# M4ToVGA.net
KiCad netlist of a schematic drawn in EAGLE
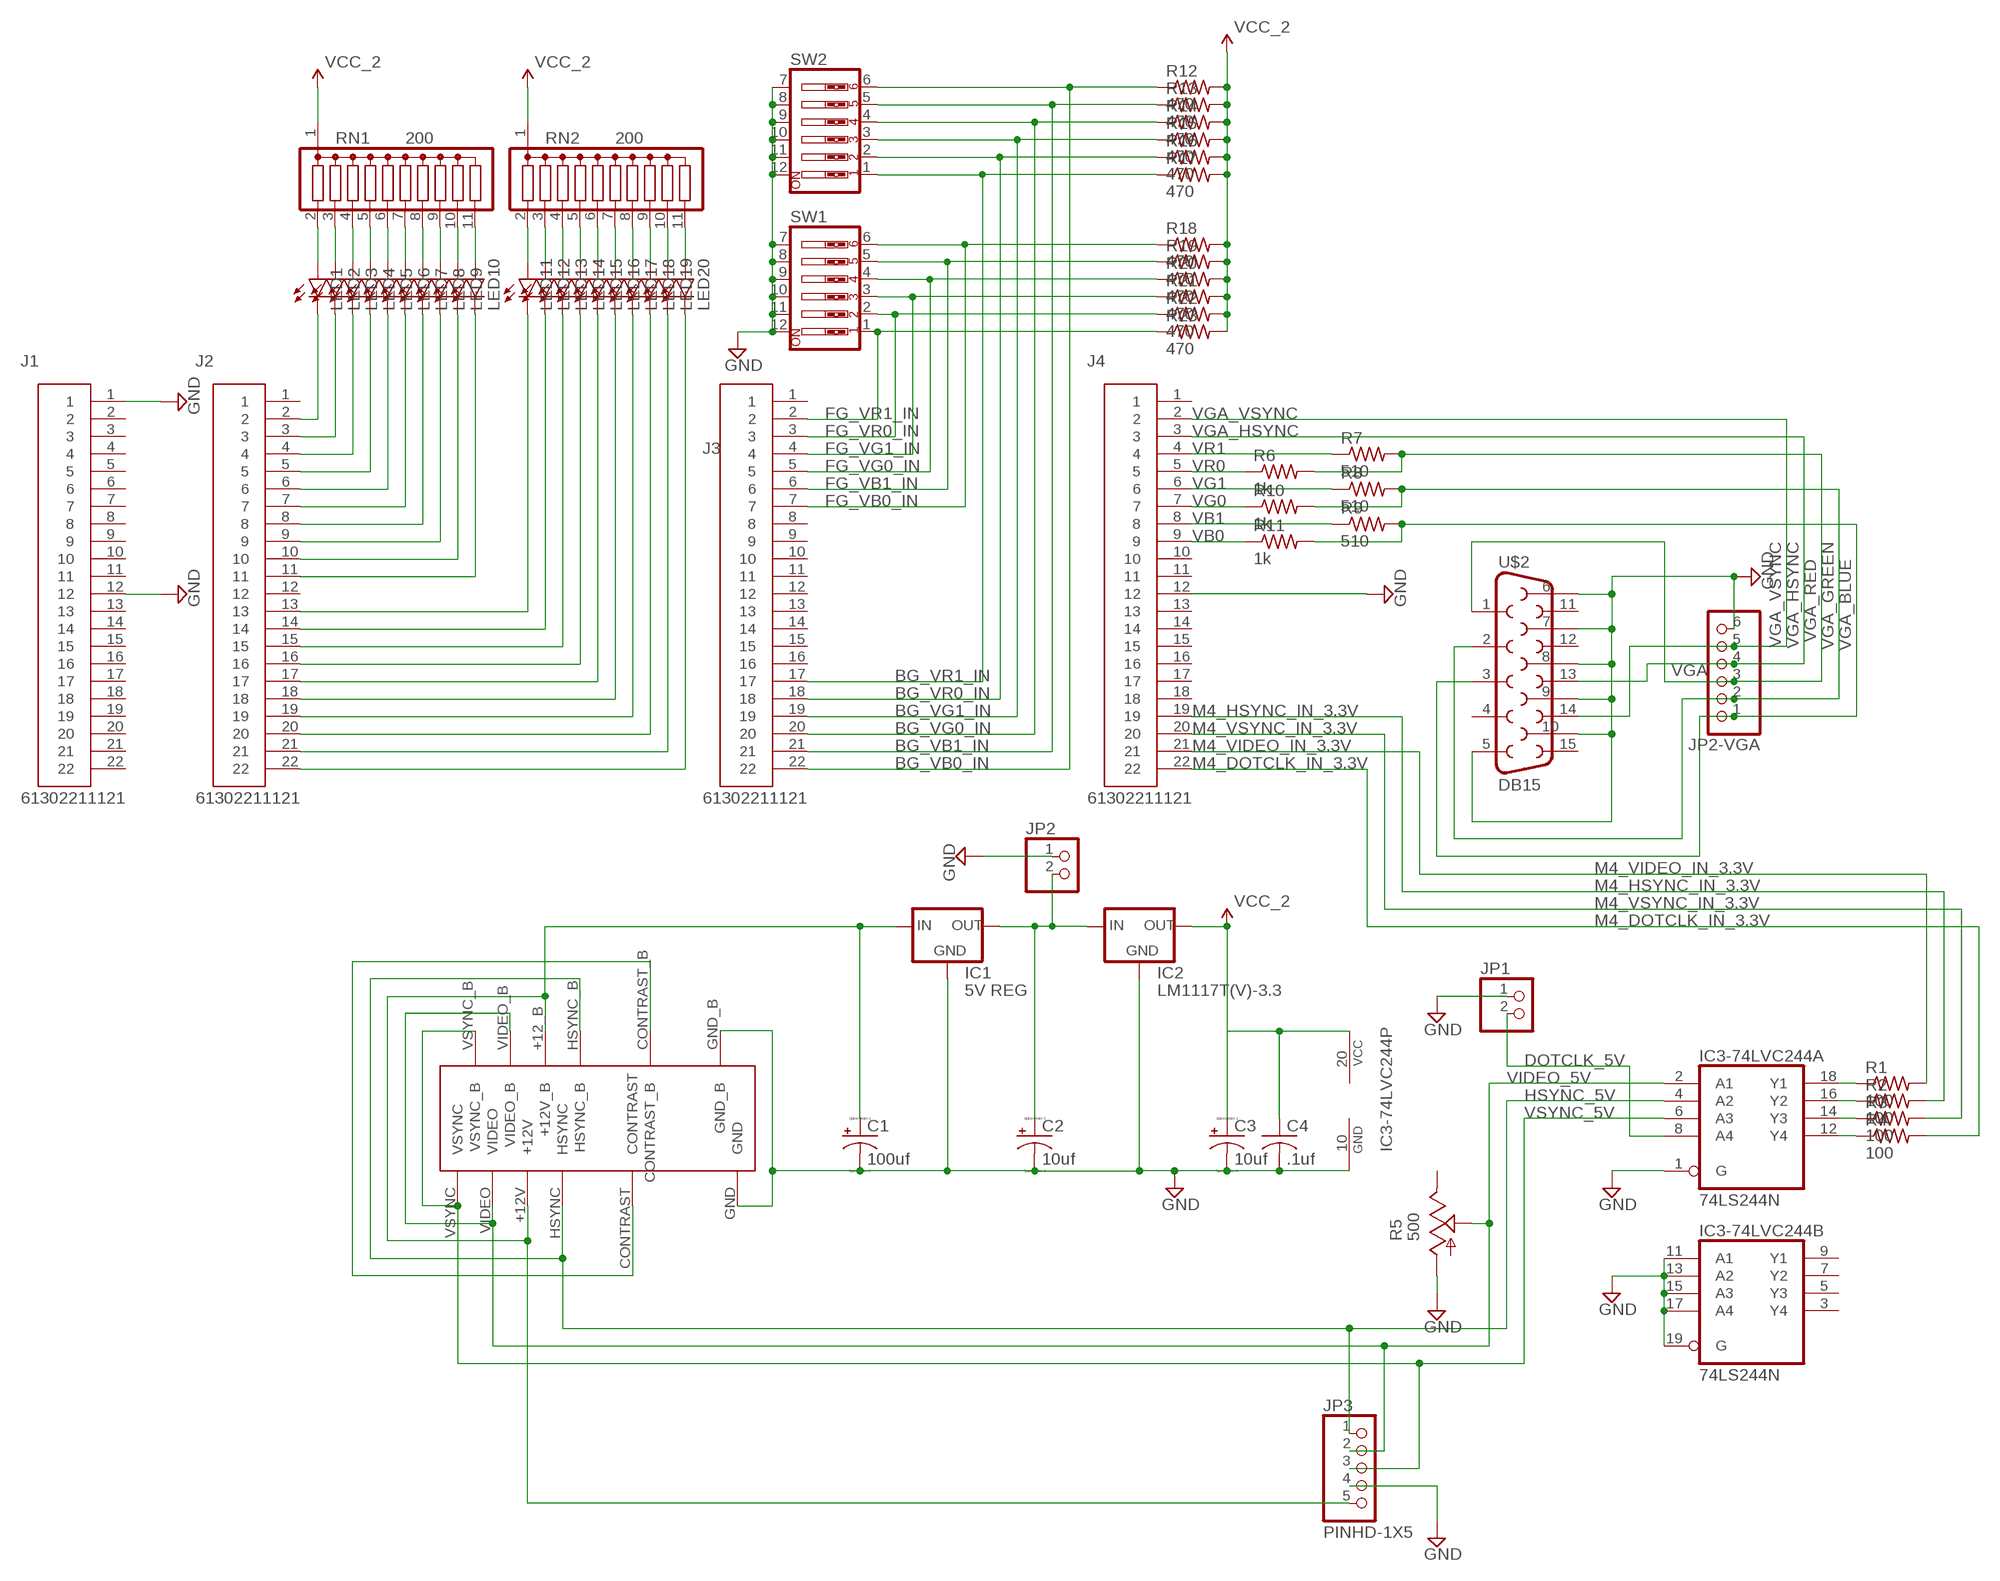
[diagram p0: schematic, sheet 1]

(export (version "E")
  (design (tool "Eeschema 10.0.6"))
  (components
    (comp (ref "C1")
      (value "100uf")
      (footprint "eagle-import:E2,5-5")
      (libsource (lib "eagle-import") (part "CPOL-USE2.5-5"))
    )
    (comp (ref "C2")
      (value "10uf")
      (footprint "eagle-import:E2,5-5")
      (libsource (lib "eagle-import") (part "CPOL-USE2.5-5"))
    )
    (comp (ref "C3")
      (value "10uf")
      (footprint "eagle-import:E2,5-5")
      (libsource (lib "eagle-import") (part "CPOL-USE2.5-5"))
    )
    (comp (ref "C4")
      (value ".1uf")
      (footprint "eagle-import:C025-025X050")
      (libsource (lib "eagle-import") (part "C-US025-025X050"))
    )
    (comp (ref "IC1")
      (value "5V REG")
      (footprint "eagle-import:78XXS")
      (libsource (lib "eagle-import") (part "78XXS"))
    )
    (comp (ref "IC2")
      (value "LM1117T(V)-3.3")
      (footprint "eagle-import:TO220V")
      (fields (field (name "MF") "Texas Instruments") (field (name "MPN") "LM1117T-3.3"))
      (libsource (lib "eagle-import") (part "LM1117?-T(V)3.3"))
    )
    (comp (ref "IC3-74LVC244")
      (value "74LS244N")
      (footprint "eagle-import:DIL20")
      (libsource (lib "eagle-import") (part "74244NLS"))
    )
    (comp (ref "J1")
      (value "61302211121")
      (footprint "eagle-import:61302211121")
      (fields
        (field (name "DIGIKEY_PART_NUMBER") "732-5330-ND")
        (field (name "MANUFACTURER") "Wurth Electronics Inc.")
        (field (name "CREATED_BY") "PCBLayout.com")
      )
      (libsource (lib "eagle-import") (part "61302211121"))
    )
    (comp (ref "J2")
      (value "61302211121")
      (footprint "eagle-import:61302211121")
      (fields
        (field (name "DIGIKEY_PART_NUMBER") "732-5330-ND")
        (field (name "MANUFACTURER") "Wurth Electronics Inc.")
        (field (name "CREATED_BY") "PCBLayout.com")
      )
      (libsource (lib "eagle-import") (part "61302211121"))
    )
    (comp (ref "J3")
      (value "61302211121")
      (footprint "eagle-import:61302211121")
      (fields
        (field (name "DIGIKEY_PART_NUMBER") "732-5330-ND")
        (field (name "MANUFACTURER") "Wurth Electronics Inc.")
        (field (name "CREATED_BY") "PCBLayout.com")
      )
      (libsource (lib "eagle-import") (part "61302211121"))
    )
    (comp (ref "J4")
      (value "61302211121")
      (footprint "eagle-import:61302211121")
      (fields
        (field (name "DIGIKEY_PART_NUMBER") "732-5330-ND")
        (field (name "MANUFACTURER") "Wurth Electronics Inc.")
        (field (name "CREATED_BY") "PCBLayout.com")
      )
      (libsource (lib "eagle-import") (part "61302211121"))
    )
    (comp (ref "JP1")
      (value "PINHD-1X2")
      (footprint "eagle-import:1X02")
      (libsource (lib "eagle-import") (part "PINHD-1X2"))
    )
    (comp (ref "JP2")
      (value "PINHD-1X2")
      (footprint "eagle-import:1X02")
      (libsource (lib "eagle-import") (part "PINHD-1X2"))
    )
    (comp (ref "JP2-VGA")
      (value "VGA")
      (footprint "eagle-import:1X06")
      (libsource (lib "eagle-import") (part "PINHD-1X6"))
    )
    (comp (ref "JP3")
      (value "PINHD-1X5")
      (footprint "eagle-import:1X05")
      (libsource (lib "eagle-import") (part "PINHD-1X5"))
    )
    (comp (ref "LED1")
      (value "LED3MM")
      (footprint "eagle-import:LED3MM")
      (libsource (lib "eagle-import") (part "LED3MM"))
    )
    (comp (ref "LED2")
      (value "LED3MM")
      (footprint "eagle-import:LED3MM")
      (libsource (lib "eagle-import") (part "LED3MM"))
    )
    (comp (ref "LED3")
      (value "LED3MM")
      (footprint "eagle-import:LED3MM")
      (libsource (lib "eagle-import") (part "LED3MM"))
    )
    (comp (ref "LED4")
      (value "LED3MM")
      (footprint "eagle-import:LED3MM")
      (libsource (lib "eagle-import") (part "LED3MM"))
    )
    (comp (ref "LED5")
      (value "LED3MM")
      (footprint "eagle-import:LED3MM")
      (libsource (lib "eagle-import") (part "LED3MM"))
    )
    (comp (ref "LED6")
      (value "LED3MM")
      (footprint "eagle-import:LED3MM")
      (libsource (lib "eagle-import") (part "LED3MM"))
    )
    (comp (ref "LED7")
      (value "LED3MM")
      (footprint "eagle-import:LED3MM")
      (libsource (lib "eagle-import") (part "LED3MM"))
    )
    (comp (ref "LED8")
      (value "LED3MM")
      (footprint "eagle-import:LED3MM")
      (libsource (lib "eagle-import") (part "LED3MM"))
    )
    (comp (ref "LED9")
      (value "LED3MM")
      (footprint "eagle-import:LED3MM")
      (libsource (lib "eagle-import") (part "LED3MM"))
    )
    (comp (ref "LED10")
      (value "LED3MM")
      (footprint "eagle-import:LED3MM")
      (libsource (lib "eagle-import") (part "LED3MM"))
    )
    (comp (ref "LED11")
      (value "LED3MM")
      (footprint "eagle-import:LED3MM")
      (libsource (lib "eagle-import") (part "LED3MM"))
    )
    (comp (ref "LED12")
      (value "LED3MM")
      (footprint "eagle-import:LED3MM")
      (libsource (lib "eagle-import") (part "LED3MM"))
    )
    (comp (ref "LED13")
      (value "LED3MM")
      (footprint "eagle-import:LED3MM")
      (libsource (lib "eagle-import") (part "LED3MM"))
    )
    (comp (ref "LED14")
      (value "LED3MM")
      (footprint "eagle-import:LED3MM")
      (libsource (lib "eagle-import") (part "LED3MM"))
    )
    (comp (ref "LED15")
      (value "LED3MM")
      (footprint "eagle-import:LED3MM")
      (libsource (lib "eagle-import") (part "LED3MM"))
    )
    (comp (ref "LED16")
      (value "LED3MM")
      (footprint "eagle-import:LED3MM")
      (libsource (lib "eagle-import") (part "LED3MM"))
    )
    (comp (ref "LED17")
      (value "LED3MM")
      (footprint "eagle-import:LED3MM")
      (libsource (lib "eagle-import") (part "LED3MM"))
    )
    (comp (ref "LED18")
      (value "LED3MM")
      (footprint "eagle-import:LED3MM")
      (libsource (lib "eagle-import") (part "LED3MM"))
    )
    (comp (ref "LED19")
      (value "LED3MM")
      (footprint "eagle-import:LED3MM")
      (libsource (lib "eagle-import") (part "LED3MM"))
    )
    (comp (ref "LED20")
      (value "LED3MM")
      (footprint "eagle-import:LED3MM")
      (libsource (lib "eagle-import") (part "LED3MM"))
    )
    (comp (ref "R1")
      (value "100")
      (footprint "eagle-import:0204_7")
      (libsource (lib "eagle-import") (part "R-US_0204/7"))
    )
    (comp (ref "R2")
      (value "100")
      (footprint "eagle-import:0204_7")
      (libsource (lib "eagle-import") (part "R-US_0204/7"))
    )
    (comp (ref "R3")
      (value "100")
      (footprint "eagle-import:0204_7")
      (libsource (lib "eagle-import") (part "R-US_0204/7"))
    )
    (comp (ref "R4")
      (value "100")
      (footprint "eagle-import:0204_7")
      (libsource (lib "eagle-import") (part "R-US_0204/7"))
    )
    (comp (ref "R5")
      (value "500")
      (footprint "eagle-import:B25P")
      (libsource (lib "eagle-import") (part "TRIM_US-B25P"))
    )
    (comp (ref "R6")
      (value "1k")
      (footprint "eagle-import:0204_7")
      (libsource (lib "eagle-import") (part "R-US_0204/7"))
    )
    (comp (ref "R7")
      (value "510")
      (footprint "eagle-import:0204_7")
      (libsource (lib "eagle-import") (part "R-US_0204/7"))
    )
    (comp (ref "R8")
      (value "510")
      (footprint "eagle-import:0204_7")
      (libsource (lib "eagle-import") (part "R-US_0204/7"))
    )
    (comp (ref "R9")
      (value "510")
      (footprint "eagle-import:0204_7")
      (libsource (lib "eagle-import") (part "R-US_0204/7"))
    )
    (comp (ref "R10")
      (value "1k")
      (footprint "eagle-import:0204_7")
      (libsource (lib "eagle-import") (part "R-US_0204/7"))
    )
    (comp (ref "R11")
      (value "1k")
      (footprint "eagle-import:0204_7")
      (libsource (lib "eagle-import") (part "R-US_0204/7"))
    )
    (comp (ref "R12")
      (value "470")
      (footprint "eagle-import:0204_7")
      (libsource (lib "eagle-import") (part "R-US_0204/7"))
    )
    (comp (ref "R13")
      (value "470")
      (footprint "eagle-import:0204_7")
      (libsource (lib "eagle-import") (part "R-US_0204/7"))
    )
    (comp (ref "R14")
      (value "470")
      (footprint "eagle-import:0204_7")
      (libsource (lib "eagle-import") (part "R-US_0204/7"))
    )
    (comp (ref "R15")
      (value "470")
      (footprint "eagle-import:0204_7")
      (libsource (lib "eagle-import") (part "R-US_0204/7"))
    )
    (comp (ref "R16")
      (value "470")
      (footprint "eagle-import:0204_7")
      (libsource (lib "eagle-import") (part "R-US_0204/7"))
    )
    (comp (ref "R17")
      (value "470")
      (footprint "eagle-import:0204_7")
      (libsource (lib "eagle-import") (part "R-US_0204/7"))
    )
    (comp (ref "R18")
      (value "470")
      (footprint "eagle-import:0204_7")
      (libsource (lib "eagle-import") (part "R-US_0204/7"))
    )
    (comp (ref "R19")
      (value "470")
      (footprint "eagle-import:0204_7")
      (libsource (lib "eagle-import") (part "R-US_0204/7"))
    )
    (comp (ref "R20")
      (value "470")
      (footprint "eagle-import:0204_7")
      (libsource (lib "eagle-import") (part "R-US_0204/7"))
    )
    (comp (ref "R21")
      (value "470")
      (footprint "eagle-import:0204_7")
      (libsource (lib "eagle-import") (part "R-US_0204/7"))
    )
    (comp (ref "R22")
      (value "470")
      (footprint "eagle-import:0204_7")
      (libsource (lib "eagle-import") (part "R-US_0204/7"))
    )
    (comp (ref "R23")
      (value "470")
      (footprint "eagle-import:0204_7")
      (libsource (lib "eagle-import") (part "R-US_0204/7"))
    )
    (comp (ref "RN1")
      (value "200")
      (footprint "eagle-import:SIL11")
      (libsource (lib "eagle-import") (part "G10R"))
    )
    (comp (ref "RN2")
      (value "200")
      (footprint "eagle-import:SIL11")
      (libsource (lib "eagle-import") (part "G10R"))
    )
    (comp (ref "SW1")
      (value "SW_DIP-6")
      (footprint "eagle-import:EDG-06")
      (libsource (lib "eagle-import") (part "SW_DIP-6"))
    )
    (comp (ref "SW2")
      (value "SW_DIP-6")
      (footprint "eagle-import:EDG-06")
      (libsource (lib "eagle-import") (part "SW_DIP-6"))
    )
    (comp (ref "U$1")
      (value "AMP-583479-1-CARD-EDGE")
      (footprint "eagle-import:AMP583479-1")
      (libsource (lib "eagle-import") (part "AMP-583479-1-CARD-EDGE"))
    )
    (comp (ref "U$2")
      (value "DB15")
      (footprint "eagle-import:DB15")
      (libsource (lib "eagle-import") (part "DB15"))
    )
  )
  (nets
    (net (code "1") (name "/BG_VB0_IN") (class "Default")
      (node (ref "J3") (pin "22") (pinfunction "22_22") (pintype "passive"))
      (node (ref "R12") (pin "1") (pinfunction "1_1") (pintype "passive"))
      (node (ref "SW2") (pin "6") (pinfunction "6_6") (pintype "passive"))
    )
    (net (code "2") (name "/BG_VB1_IN") (class "Default")
      (node (ref "J3") (pin "21") (pinfunction "21_21") (pintype "passive"))
      (node (ref "R13") (pin "1") (pinfunction "1_1") (pintype "passive"))
      (node (ref "SW2") (pin "5") (pinfunction "5_5") (pintype "passive"))
    )
    (net (code "3") (name "/BG_VG0_IN") (class "Default")
      (node (ref "J3") (pin "20") (pinfunction "20_20") (pintype "passive"))
      (node (ref "R14") (pin "1") (pinfunction "1_1") (pintype "passive"))
      (node (ref "SW2") (pin "4") (pinfunction "4_4") (pintype "passive"))
    )
    (net (code "4") (name "/BG_VG1_IN") (class "Default")
      (node (ref "J3") (pin "19") (pinfunction "19_19") (pintype "passive"))
      (node (ref "R15") (pin "1") (pinfunction "1_1") (pintype "passive"))
      (node (ref "SW2") (pin "3") (pinfunction "3_3") (pintype "passive"))
    )
    (net (code "5") (name "/BG_VR0_IN") (class "Default")
      (node (ref "J3") (pin "18") (pinfunction "18_18") (pintype "passive"))
      (node (ref "R16") (pin "1") (pinfunction "1_1") (pintype "passive"))
      (node (ref "SW2") (pin "2") (pinfunction "2_2") (pintype "passive"))
    )
    (net (code "6") (name "/BG_VR1_IN") (class "Default")
      (node (ref "J3") (pin "17") (pinfunction "17_17") (pintype "passive"))
      (node (ref "R17") (pin "1") (pinfunction "1_1") (pintype "passive"))
      (node (ref "SW2") (pin "1") (pinfunction "1_1") (pintype "passive"))
    )
    (net (code "7") (name "/DOTCLK_5V") (class "Default")
      (node (ref "IC3-74LVC244") (pin "8") (pinfunction "A4_8") (pintype "input"))
      (node (ref "JP1") (pin "2") (pinfunction "2_2") (pintype "passive"))
    )
    (net (code "8") (name "/FG_VB0_IN") (class "Default")
      (node (ref "J3") (pin "7") (pinfunction "7_7") (pintype "passive"))
      (node (ref "R18") (pin "1") (pinfunction "1_1") (pintype "passive"))
      (node (ref "SW1") (pin "6") (pinfunction "6_6") (pintype "passive"))
    )
    (net (code "9") (name "/FG_VB1_IN") (class "Default")
      (node (ref "J3") (pin "6") (pinfunction "6_6") (pintype "passive"))
      (node (ref "R19") (pin "1") (pinfunction "1_1") (pintype "passive"))
      (node (ref "SW1") (pin "5") (pinfunction "5_5") (pintype "passive"))
    )
    (net (code "10") (name "/FG_VG0_IN") (class "Default")
      (node (ref "J3") (pin "5") (pinfunction "5_5") (pintype "passive"))
      (node (ref "R20") (pin "1") (pinfunction "1_1") (pintype "passive"))
      (node (ref "SW1") (pin "4") (pinfunction "4_4") (pintype "passive"))
    )
    (net (code "11") (name "/FG_VG1_IN") (class "Default")
      (node (ref "J3") (pin "4") (pinfunction "4_4") (pintype "passive"))
      (node (ref "R21") (pin "1") (pinfunction "1_1") (pintype "passive"))
      (node (ref "SW1") (pin "3") (pinfunction "3_3") (pintype "passive"))
    )
    (net (code "12") (name "/FG_VR0_IN") (class "Default")
      (node (ref "J3") (pin "3") (pinfunction "3_3") (pintype "passive"))
      (node (ref "R22") (pin "1") (pinfunction "1_1") (pintype "passive"))
      (node (ref "SW1") (pin "2") (pinfunction "2_2") (pintype "passive"))
    )
    (net (code "13") (name "/FG_VR1_IN") (class "Default")
      (node (ref "J3") (pin "2") (pinfunction "2_2") (pintype "passive"))
      (node (ref "R23") (pin "1") (pinfunction "1_1") (pintype "passive"))
      (node (ref "SW1") (pin "1") (pinfunction "1_1") (pintype "passive"))
    )
    (net (code "14") (name "/HSYNC_5V") (class "Default")
      (node (ref "IC3-74LVC244") (pin "4") (pinfunction "A2_4") (pintype "input"))
      (node (ref "JP3") (pin "1") (pinfunction "1_1") (pintype "passive"))
      (node (ref "U$1") (pin "HSYNC") (pinfunction "HSYNC_HSYNC") (pintype "bidirectional"))
      (node (ref "U$1") (pin "HSYNC_B") (pinfunction "HSYNC_B_HSYNC_B") (pintype "bidirectional"))
    )
    (net (code "15") (name "/M4_DOTCLK_IN_3.3V") (class "Default")
      (node (ref "J4") (pin "22") (pinfunction "22_22") (pintype "passive"))
      (node (ref "R4") (pin "2") (pinfunction "2_2") (pintype "passive"))
    )
    (net (code "16") (name "/M4_HSYNC_IN_3.3V") (class "Default")
      (node (ref "J4") (pin "19") (pinfunction "19_19") (pintype "passive"))
      (node (ref "R2") (pin "2") (pinfunction "2_2") (pintype "passive"))
    )
    (net (code "17") (name "/M4_VIDEO_IN_3.3V") (class "Default")
      (node (ref "J4") (pin "21") (pinfunction "21_21") (pintype "passive"))
      (node (ref "R1") (pin "2") (pinfunction "2_2") (pintype "passive"))
    )
    (net (code "18") (name "/M4_VSYNC_IN_3.3V") (class "Default")
      (node (ref "J4") (pin "20") (pinfunction "20_20") (pintype "passive"))
      (node (ref "R3") (pin "2") (pinfunction "2_2") (pintype "passive"))
    )
    (net (code "19") (name "/VB0") (class "Default")
      (node (ref "J4") (pin "9") (pinfunction "9_9") (pintype "passive"))
      (node (ref "R11") (pin "1") (pinfunction "1_1") (pintype "passive"))
    )
    (net (code "20") (name "/VB1") (class "Default")
      (node (ref "J4") (pin "8") (pinfunction "8_8") (pintype "passive"))
      (node (ref "R9") (pin "1") (pinfunction "1_1") (pintype "passive"))
    )
    (net (code "21") (name "/VG0") (class "Default")
      (node (ref "J4") (pin "7") (pinfunction "7_7") (pintype "passive"))
      (node (ref "R10") (pin "1") (pinfunction "1_1") (pintype "passive"))
    )
    (net (code "22") (name "/VG1") (class "Default")
      (node (ref "J4") (pin "6") (pinfunction "6_6") (pintype "passive"))
      (node (ref "R8") (pin "1") (pinfunction "1_1") (pintype "passive"))
    )
    (net (code "23") (name "/VGA_BLUE") (class "Default")
      (node (ref "JP2-VGA") (pin "1") (pinfunction "1_1") (pintype "passive"))
      (node (ref "R11") (pin "2") (pinfunction "2_2") (pintype "passive"))
      (node (ref "R9") (pin "2") (pinfunction "2_2") (pintype "passive"))
      (node (ref "U$2") (pin "3") (pinfunction "3_3") (pintype "passive"))
    )
    (net (code "24") (name "/VGA_GREEN") (class "Default")
      (node (ref "JP2-VGA") (pin "2") (pinfunction "2_2") (pintype "passive"))
      (node (ref "R10") (pin "2") (pinfunction "2_2") (pintype "passive"))
      (node (ref "R8") (pin "2") (pinfunction "2_2") (pintype "passive"))
      (node (ref "U$2") (pin "2") (pinfunction "2_2") (pintype "passive"))
    )
    (net (code "25") (name "/VGA_HSYNC") (class "Default")
      (node (ref "J4") (pin "3") (pinfunction "3_3") (pintype "passive"))
      (node (ref "JP2-VGA") (pin "4") (pinfunction "4_4") (pintype "passive"))
      (node (ref "U$2") (pin "13") (pinfunction "13_13") (pintype "passive"))
    )
    (net (code "26") (name "/VGA_RED") (class "Default")
      (node (ref "JP2-VGA") (pin "3") (pinfunction "3_3") (pintype "passive"))
      (node (ref "R6") (pin "2") (pinfunction "2_2") (pintype "passive"))
      (node (ref "R7") (pin "2") (pinfunction "2_2") (pintype "passive"))
      (node (ref "U$2") (pin "1") (pinfunction "1_1") (pintype "passive"))
    )
    (net (code "27") (name "/VGA_VSYNC") (class "Default")
      (node (ref "J4") (pin "2") (pinfunction "2_2") (pintype "passive"))
      (node (ref "JP2-VGA") (pin "5") (pinfunction "5_5") (pintype "passive"))
      (node (ref "U$2") (pin "14") (pinfunction "14_14") (pintype "passive"))
    )
    (net (code "28") (name "/VIDEO_5V") (class "Default")
      (node (ref "IC3-74LVC244") (pin "2") (pinfunction "A1_2") (pintype "input"))
      (node (ref "JP3") (pin "2") (pinfunction "2_2") (pintype "passive"))
      (node (ref "R5") (pin "S") (pinfunction "S_S") (pintype "passive"))
      (node (ref "U$1") (pin "VIDEO") (pinfunction "VIDEO_VIDEO") (pintype "bidirectional"))
      (node (ref "U$1") (pin "VIDEO_B") (pinfunction "VIDEO_B_VIDEO_B") (pintype "bidirectional"))
    )
    (net (code "29") (name "/VR0") (class "Default")
      (node (ref "J4") (pin "5") (pinfunction "5_5") (pintype "passive"))
      (node (ref "R6") (pin "1") (pinfunction "1_1") (pintype "passive"))
    )
    (net (code "30") (name "/VR1") (class "Default")
      (node (ref "J4") (pin "4") (pinfunction "4_4") (pintype "passive"))
      (node (ref "R7") (pin "1") (pinfunction "1_1") (pintype "passive"))
    )
    (net (code "31") (name "/VSYNC_5V") (class "Default")
      (node (ref "IC3-74LVC244") (pin "6") (pinfunction "A3_6") (pintype "input"))
      (node (ref "JP3") (pin "3") (pinfunction "3_3") (pintype "passive"))
      (node (ref "U$1") (pin "VSYNC") (pinfunction "VSYNC_VSYNC") (pintype "bidirectional"))
      (node (ref "U$1") (pin "VSYNC_B") (pinfunction "VSYNC_B_VSYNC_B") (pintype "bidirectional"))
    )
    (net (code "32") (name "GND") (class "Default")
      (node (ref "C1") (pin "-") (pinfunction "-_-") (pintype "passive"))
      (node (ref "C2") (pin "-") (pinfunction "-_-") (pintype "passive"))
      (node (ref "C3") (pin "-") (pinfunction "-_-") (pintype "passive"))
      (node (ref "C4") (pin "2") (pinfunction "2_2") (pintype "passive"))
      (node (ref "IC1") (pin "GND") (pinfunction "GND_GND") (pintype "input"))
      (node (ref "IC2") (pin "1") (pinfunction "GND_1") (pintype "input"))
      (node (ref "IC3-74LVC244") (pin "1") (pinfunction "G_1") (pintype "input"))
      (node (ref "IC3-74LVC244") (pin "10") (pinfunction "GND_10") (pintype "power_in"))
      (node (ref "IC3-74LVC244") (pin "11") (pinfunction "A1_11") (pintype "input"))
      (node (ref "IC3-74LVC244") (pin "13") (pinfunction "A2_13") (pintype "input"))
      (node (ref "IC3-74LVC244") (pin "15") (pinfunction "A3_15") (pintype "input"))
      (node (ref "IC3-74LVC244") (pin "17") (pinfunction "A4_17") (pintype "input"))
      (node (ref "IC3-74LVC244") (pin "19") (pinfunction "G_19") (pintype "input"))
      (node (ref "J1") (pin "1") (pinfunction "1_1") (pintype "passive"))
      (node (ref "J1") (pin "12") (pinfunction "12_12") (pintype "passive"))
      (node (ref "J4") (pin "12") (pinfunction "12_12") (pintype "passive"))
      (node (ref "JP1") (pin "1") (pinfunction "1_1") (pintype "passive"))
      (node (ref "JP2") (pin "1") (pinfunction "1_1") (pintype "passive"))
      (node (ref "JP2-VGA") (pin "6") (pinfunction "6_6") (pintype "passive"))
      (node (ref "JP3") (pin "4") (pinfunction "4_4") (pintype "passive"))
      (node (ref "R5") (pin "A") (pinfunction "A_A") (pintype "passive"))
      (node (ref "SW1") (pin "10") (pinfunction "10_10") (pintype "passive"))
      (node (ref "SW1") (pin "11") (pinfunction "11_11") (pintype "passive"))
      (node (ref "SW1") (pin "12") (pinfunction "12_12") (pintype "passive"))
      (node (ref "SW1") (pin "7") (pinfunction "7_7") (pintype "passive"))
      (node (ref "SW1") (pin "8") (pinfunction "8_8") (pintype "passive"))
      (node (ref "SW1") (pin "9") (pinfunction "9_9") (pintype "passive"))
      (node (ref "SW2") (pin "10") (pinfunction "10_10") (pintype "passive"))
      (node (ref "SW2") (pin "11") (pinfunction "11_11") (pintype "passive"))
      (node (ref "SW2") (pin "12") (pinfunction "12_12") (pintype "passive"))
      (node (ref "SW2") (pin "7") (pinfunction "7_7") (pintype "passive"))
      (node (ref "SW2") (pin "8") (pinfunction "8_8") (pintype "passive"))
      (node (ref "SW2") (pin "9") (pinfunction "9_9") (pintype "passive"))
      (node (ref "U$1") (pin "GND") (pinfunction "GND_GND") (pintype "bidirectional"))
      (node (ref "U$1") (pin "GND_B") (pinfunction "GND_B_GND_B") (pintype "bidirectional"))
      (node (ref "U$2") (pin "10") (pinfunction "10_10") (pintype "passive"))
      (node (ref "U$2") (pin "5") (pinfunction "5_5") (pintype "passive"))
      (node (ref "U$2") (pin "6") (pinfunction "6_6") (pintype "passive"))
      (node (ref "U$2") (pin "7") (pinfunction "7_7") (pintype "passive"))
      (node (ref "U$2") (pin "8") (pinfunction "8_8") (pintype "passive"))
      (node (ref "U$2") (pin "9") (pinfunction "9_9") (pintype "passive"))
    )
    (net (code "33") (name "Net-(IC2-IN)") (class "Default")
      (node (ref "C2") (pin "+") (pinfunction "+_+") (pintype "passive"))
      (node (ref "IC1") (pin "OUT") (pinfunction "OUT_OUT") (pintype "passive"))
      (node (ref "IC2") (pin "3") (pinfunction "IN_3") (pintype "input"))
      (node (ref "JP2") (pin "2") (pinfunction "2_2") (pintype "passive"))
    )
    (net (code "34") (name "Net-(IC3-74LVC244A-Y1)") (class "Default")
      (node (ref "IC3-74LVC244") (pin "18") (pinfunction "Y1_18") (pintype "tri_state"))
      (node (ref "R1") (pin "1") (pinfunction "1_1") (pintype "passive"))
    )
    (net (code "35") (name "Net-(IC3-74LVC244A-Y2)") (class "Default")
      (node (ref "IC3-74LVC244") (pin "16") (pinfunction "Y2_16") (pintype "tri_state"))
      (node (ref "R2") (pin "1") (pinfunction "1_1") (pintype "passive"))
    )
    (net (code "36") (name "Net-(IC3-74LVC244A-Y3)") (class "Default")
      (node (ref "IC3-74LVC244") (pin "14") (pinfunction "Y3_14") (pintype "tri_state"))
      (node (ref "R3") (pin "1") (pinfunction "1_1") (pintype "passive"))
    )
    (net (code "37") (name "Net-(IC3-74LVC244A-Y4)") (class "Default")
      (node (ref "IC3-74LVC244") (pin "12") (pinfunction "Y4_12") (pintype "tri_state"))
      (node (ref "R4") (pin "1") (pinfunction "1_1") (pintype "passive"))
    )
    (net (code "38") (name "Net-(LED1-C)") (class "Default")
      (node (ref "J2") (pin "2") (pinfunction "2_2") (pintype "passive"))
      (node (ref "LED1") (pin "K") (pinfunction "C_K") (pintype "passive"))
    )
    (net (code "39") (name "Net-(LED1-PadA)") (class "Default")
      (node (ref "LED1") (pin "A") (pinfunction "A_A") (pintype "passive"))
      (node (ref "RN1") (pin "2") (pinfunction "2_2") (pintype "passive"))
    )
    (net (code "40") (name "Net-(LED2-C)") (class "Default")
      (node (ref "J2") (pin "3") (pinfunction "3_3") (pintype "passive"))
      (node (ref "LED2") (pin "K") (pinfunction "C_K") (pintype "passive"))
    )
    (net (code "41") (name "Net-(LED2-PadA)") (class "Default")
      (node (ref "LED2") (pin "A") (pinfunction "A_A") (pintype "passive"))
      (node (ref "RN1") (pin "3") (pinfunction "3_3") (pintype "passive"))
    )
    (net (code "42") (name "Net-(LED3-C)") (class "Default")
      (node (ref "J2") (pin "4") (pinfunction "4_4") (pintype "passive"))
      (node (ref "LED3") (pin "K") (pinfunction "C_K") (pintype "passive"))
    )
    (net (code "43") (name "Net-(LED3-PadA)") (class "Default")
      (node (ref "LED3") (pin "A") (pinfunction "A_A") (pintype "passive"))
      (node (ref "RN1") (pin "4") (pinfunction "4_4") (pintype "passive"))
    )
    (net (code "44") (name "Net-(LED4-C)") (class "Default")
      (node (ref "J2") (pin "5") (pinfunction "5_5") (pintype "passive"))
      (node (ref "LED4") (pin "K") (pinfunction "C_K") (pintype "passive"))
    )
    (net (code "45") (name "Net-(LED4-PadA)") (class "Default")
      (node (ref "LED4") (pin "A") (pinfunction "A_A") (pintype "passive"))
      (node (ref "RN1") (pin "5") (pinfunction "5_5") (pintype "passive"))
    )
    (net (code "46") (name "Net-(LED5-C)") (class "Default")
      (node (ref "J2") (pin "6") (pinfunction "6_6") (pintype "passive"))
      (node (ref "LED5") (pin "K") (pinfunction "C_K") (pintype "passive"))
    )
    (net (code "47") (name "Net-(LED5-PadA)") (class "Default")
      (node (ref "LED5") (pin "A") (pinfunction "A_A") (pintype "passive"))
      (node (ref "RN1") (pin "6") (pinfunction "6_6") (pintype "passive"))
    )
    (net (code "48") (name "Net-(LED6-C)") (class "Default")
      (node (ref "J2") (pin "7") (pinfunction "7_7") (pintype "passive"))
      (node (ref "LED6") (pin "K") (pinfunction "C_K") (pintype "passive"))
    )
    (net (code "49") (name "Net-(LED6-PadA)") (class "Default")
      (node (ref "LED6") (pin "A") (pinfunction "A_A") (pintype "passive"))
      (node (ref "RN1") (pin "7") (pinfunction "7_7") (pintype "passive"))
    )
    (net (code "50") (name "Net-(LED7-C)") (class "Default")
      (node (ref "J2") (pin "8") (pinfunction "8_8") (pintype "passive"))
      (node (ref "LED7") (pin "K") (pinfunction "C_K") (pintype "passive"))
    )
    (net (code "51") (name "Net-(LED7-PadA)") (class "Default")
      (node (ref "LED7") (pin "A") (pinfunction "A_A") (pintype "passive"))
      (node (ref "RN1") (pin "8") (pinfunction "8_8") (pintype "passive"))
    )
    (net (code "52") (name "Net-(LED8-C)") (class "Default")
      (node (ref "J2") (pin "9") (pinfunction "9_9") (pintype "passive"))
      (node (ref "LED8") (pin "K") (pinfunction "C_K") (pintype "passive"))
    )
    (net (code "53") (name "Net-(LED8-PadA)") (class "Default")
      (node (ref "LED8") (pin "A") (pinfunction "A_A") (pintype "passive"))
      (node (ref "RN1") (pin "9") (pinfunction "9_9") (pintype "passive"))
    )
    (net (code "54") (name "Net-(LED9-C)") (class "Default")
      (node (ref "J2") (pin "10") (pinfunction "10_10") (pintype "passive"))
      (node (ref "LED9") (pin "K") (pinfunction "C_K") (pintype "passive"))
    )
    (net (code "55") (name "Net-(LED9-PadA)") (class "Default")
      (node (ref "LED9") (pin "A") (pinfunction "A_A") (pintype "passive"))
      (node (ref "RN1") (pin "10") (pinfunction "10_10") (pintype "passive"))
    )
    (net (code "56") (name "Net-(LED10-C)") (class "Default")
      (node (ref "J2") (pin "11") (pinfunction "11_11") (pintype "passive"))
      (node (ref "LED10") (pin "K") (pinfunction "C_K") (pintype "passive"))
    )
    (net (code "57") (name "Net-(LED10-PadA)") (class "Default")
      (node (ref "LED10") (pin "A") (pinfunction "A_A") (pintype "passive"))
      (node (ref "RN1") (pin "11") (pinfunction "11_11") (pintype "passive"))
    )
    (net (code "58") (name "Net-(LED11-C)") (class "Default")
      (node (ref "J2") (pin "13") (pinfunction "13_13") (pintype "passive"))
      (node (ref "LED11") (pin "K") (pinfunction "C_K") (pintype "passive"))
    )
    (net (code "59") (name "Net-(LED11-PadA)") (class "Default")
      (node (ref "LED11") (pin "A") (pinfunction "A_A") (pintype "passive"))
      (node (ref "RN2") (pin "2") (pinfunction "2_2") (pintype "passive"))
    )
    (net (code "60") (name "Net-(LED12-C)") (class "Default")
      (node (ref "J2") (pin "14") (pinfunction "14_14") (pintype "passive"))
      (node (ref "LED12") (pin "K") (pinfunction "C_K") (pintype "passive"))
    )
    (net (code "61") (name "Net-(LED12-PadA)") (class "Default")
      (node (ref "LED12") (pin "A") (pinfunction "A_A") (pintype "passive"))
      (node (ref "RN2") (pin "3") (pinfunction "3_3") (pintype "passive"))
    )
    (net (code "62") (name "Net-(LED13-C)") (class "Default")
      (node (ref "J2") (pin "15") (pinfunction "15_15") (pintype "passive"))
      (node (ref "LED13") (pin "K") (pinfunction "C_K") (pintype "passive"))
    )
    (net (code "63") (name "Net-(LED13-PadA)") (class "Default")
      (node (ref "LED13") (pin "A") (pinfunction "A_A") (pintype "passive"))
      (node (ref "RN2") (pin "4") (pinfunction "4_4") (pintype "passive"))
    )
    (net (code "64") (name "Net-(LED14-C)") (class "Default")
      (node (ref "J2") (pin "16") (pinfunction "16_16") (pintype "passive"))
      (node (ref "LED14") (pin "K") (pinfunction "C_K") (pintype "passive"))
    )
    (net (code "65") (name "Net-(LED14-PadA)") (class "Default")
      (node (ref "LED14") (pin "A") (pinfunction "A_A") (pintype "passive"))
      (node (ref "RN2") (pin "5") (pinfunction "5_5") (pintype "passive"))
    )
    (net (code "66") (name "Net-(LED15-C)") (class "Default")
      (node (ref "J2") (pin "17") (pinfunction "17_17") (pintype "passive"))
      (node (ref "LED15") (pin "K") (pinfunction "C_K") (pintype "passive"))
    )
    (net (code "67") (name "Net-(LED15-PadA)") (class "Default")
      (node (ref "LED15") (pin "A") (pinfunction "A_A") (pintype "passive"))
      (node (ref "RN2") (pin "6") (pinfunction "6_6") (pintype "passive"))
    )
    (net (code "68") (name "Net-(LED16-C)") (class "Default")
      (node (ref "J2") (pin "18") (pinfunction "18_18") (pintype "passive"))
      (node (ref "LED16") (pin "K") (pinfunction "C_K") (pintype "passive"))
    )
    (net (code "69") (name "Net-(LED16-PadA)") (class "Default")
      (node (ref "LED16") (pin "A") (pinfunction "A_A") (pintype "passive"))
      (node (ref "RN2") (pin "7") (pinfunction "7_7") (pintype "passive"))
    )
    (net (code "70") (name "Net-(LED17-C)") (class "Default")
      (node (ref "J2") (pin "19") (pinfunction "19_19") (pintype "passive"))
      (node (ref "LED17") (pin "K") (pinfunction "C_K") (pintype "passive"))
    )
    (net (code "71") (name "Net-(LED17-PadA)") (class "Default")
      (node (ref "LED17") (pin "A") (pinfunction "A_A") (pintype "passive"))
      (node (ref "RN2") (pin "8") (pinfunction "8_8") (pintype "passive"))
    )
    (net (code "72") (name "Net-(LED18-C)") (class "Default")
      (node (ref "J2") (pin "20") (pinfunction "20_20") (pintype "passive"))
      (node (ref "LED18") (pin "K") (pinfunction "C_K") (pintype "passive"))
    )
    (net (code "73") (name "Net-(LED18-PadA)") (class "Default")
      (node (ref "LED18") (pin "A") (pinfunction "A_A") (pintype "passive"))
      (node (ref "RN2") (pin "9") (pinfunction "9_9") (pintype "passive"))
    )
    (net (code "74") (name "Net-(LED19-C)") (class "Default")
      (node (ref "J2") (pin "21") (pinfunction "21_21") (pintype "passive"))
      (node (ref "LED19") (pin "K") (pinfunction "C_K") (pintype "passive"))
    )
    (net (code "75") (name "Net-(LED19-PadA)") (class "Default")
      (node (ref "LED19") (pin "A") (pinfunction "A_A") (pintype "passive"))
      (node (ref "RN2") (pin "10") (pinfunction "10_10") (pintype "passive"))
    )
    (net (code "76") (name "Net-(LED20-C)") (class "Default")
      (node (ref "J2") (pin "22") (pinfunction "22_22") (pintype "passive"))
      (node (ref "LED20") (pin "K") (pinfunction "C_K") (pintype "passive"))
    )
    (net (code "77") (name "Net-(LED20-PadA)") (class "Default")
      (node (ref "LED20") (pin "A") (pinfunction "A_A") (pintype "passive"))
      (node (ref "RN2") (pin "11") (pinfunction "11_11") (pintype "passive"))
    )
    (net (code "78") (name "Net-(U$1-+12V_B)") (class "Default")
      (node (ref "C1") (pin "+") (pinfunction "+_+") (pintype "passive"))
      (node (ref "IC1") (pin "IN") (pinfunction "IN_IN") (pintype "input"))
      (node (ref "JP3") (pin "5") (pinfunction "5_5") (pintype "passive"))
      (node (ref "U$1") (pin "+12V") (pinfunction "+12V_+12V") (pintype "bidirectional"))
      (node (ref "U$1") (pin "+12_B") (pinfunction "+12V_B_+12_B") (pintype "bidirectional"))
    )
    (net (code "79") (name "Net-(U$1-PadCONTRAST)") (class "Default")
      (node (ref "U$1") (pin "CONTRAST") (pinfunction "CONTRAST_CONTRAST") (pintype "bidirectional"))
      (node (ref "U$1") (pin "CONTRAST_B") (pinfunction "CONTRAST_B_CONTRAST_B") (pintype "bidirectional"))
    )
    (net (code "80") (name "VCC_2") (class "Default")
      (node (ref "C3") (pin "+") (pinfunction "+_+") (pintype "passive"))
      (node (ref "C4") (pin "1") (pinfunction "1_1") (pintype "passive"))
      (node (ref "IC2") (pin "2") (pinfunction "OUT_2") (pintype "passive"))
      (node (ref "IC3-74LVC244") (pin "20") (pinfunction "VCC_20") (pintype "power_in"))
      (node (ref "R12") (pin "2") (pinfunction "2_2") (pintype "passive"))
      (node (ref "R13") (pin "2") (pinfunction "2_2") (pintype "passive"))
      (node (ref "R14") (pin "2") (pinfunction "2_2") (pintype "passive"))
      (node (ref "R15") (pin "2") (pinfunction "2_2") (pintype "passive"))
      (node (ref "R16") (pin "2") (pinfunction "2_2") (pintype "passive"))
      (node (ref "R17") (pin "2") (pinfunction "2_2") (pintype "passive"))
      (node (ref "R18") (pin "2") (pinfunction "2_2") (pintype "passive"))
      (node (ref "R19") (pin "2") (pinfunction "2_2") (pintype "passive"))
      (node (ref "R20") (pin "2") (pinfunction "2_2") (pintype "passive"))
      (node (ref "R21") (pin "2") (pinfunction "2_2") (pintype "passive"))
      (node (ref "R22") (pin "2") (pinfunction "2_2") (pintype "passive"))
      (node (ref "R23") (pin "2") (pinfunction "2_2") (pintype "passive"))
      (node (ref "RN1") (pin "1") (pinfunction "1_1") (pintype "passive"))
      (node (ref "RN2") (pin "1") (pinfunction "1_1") (pintype "passive"))
    )
    (net (code "81") (name "unconnected-(IC3-74LVC244B-Y1-Pad9)") (class "Default")
      (node (ref "IC3-74LVC244") (pin "9") (pinfunction "Y1_9") (pintype "tri_state"))
    )
    (net (code "82") (name "unconnected-(IC3-74LVC244B-Y2-Pad7)") (class "Default")
      (node (ref "IC3-74LVC244") (pin "7") (pinfunction "Y2_7") (pintype "tri_state"))
    )
    (net (code "83") (name "unconnected-(IC3-74LVC244B-Y3-Pad5)") (class "Default")
      (node (ref "IC3-74LVC244") (pin "5") (pinfunction "Y3_5") (pintype "tri_state"))
    )
    (net (code "84") (name "unconnected-(IC3-74LVC244B-Y4-Pad3)") (class "Default")
      (node (ref "IC3-74LVC244") (pin "3") (pinfunction "Y4_3") (pintype "tri_state"))
    )
    (net (code "85") (name "unconnected-(J1-Pad2)") (class "Default")
      (node (ref "J1") (pin "2") (pinfunction "2_2") (pintype "passive"))
    )
    (net (code "86") (name "unconnected-(J1-Pad3)") (class "Default")
      (node (ref "J1") (pin "3") (pinfunction "3_3") (pintype "passive"))
    )
    (net (code "87") (name "unconnected-(J1-Pad4)") (class "Default")
      (node (ref "J1") (pin "4") (pinfunction "4_4") (pintype "passive"))
    )
    (net (code "88") (name "unconnected-(J1-Pad5)") (class "Default")
      (node (ref "J1") (pin "5") (pinfunction "5_5") (pintype "passive"))
    )
    (net (code "89") (name "unconnected-(J1-Pad6)") (class "Default")
      (node (ref "J1") (pin "6") (pinfunction "6_6") (pintype "passive"))
    )
    (net (code "90") (name "unconnected-(J1-Pad7)") (class "Default")
      (node (ref "J1") (pin "7") (pinfunction "7_7") (pintype "passive"))
    )
    (net (code "91") (name "unconnected-(J1-Pad8)") (class "Default")
      (node (ref "J1") (pin "8") (pinfunction "8_8") (pintype "passive"))
    )
    (net (code "92") (name "unconnected-(J1-Pad9)") (class "Default")
      (node (ref "J1") (pin "9") (pinfunction "9_9") (pintype "passive"))
    )
    (net (code "93") (name "unconnected-(J1-Pad10)") (class "Default")
      (node (ref "J1") (pin "10") (pinfunction "10_10") (pintype "passive"))
    )
    (net (code "94") (name "unconnected-(J1-Pad11)") (class "Default")
      (node (ref "J1") (pin "11") (pinfunction "11_11") (pintype "passive"))
    )
    (net (code "95") (name "unconnected-(J1-Pad13)") (class "Default")
      (node (ref "J1") (pin "13") (pinfunction "13_13") (pintype "passive"))
    )
    (net (code "96") (name "unconnected-(J1-Pad14)") (class "Default")
      (node (ref "J1") (pin "14") (pinfunction "14_14") (pintype "passive"))
    )
    (net (code "97") (name "unconnected-(J1-Pad15)") (class "Default")
      (node (ref "J1") (pin "15") (pinfunction "15_15") (pintype "passive"))
    )
    (net (code "98") (name "unconnected-(J1-Pad16)") (class "Default")
      (node (ref "J1") (pin "16") (pinfunction "16_16") (pintype "passive"))
    )
    (net (code "99") (name "unconnected-(J1-Pad17)") (class "Default")
      (node (ref "J1") (pin "17") (pinfunction "17_17") (pintype "passive"))
    )
    (net (code "100") (name "unconnected-(J1-Pad18)") (class "Default")
      (node (ref "J1") (pin "18") (pinfunction "18_18") (pintype "passive"))
    )
    (net (code "101") (name "unconnected-(J1-Pad19)") (class "Default")
      (node (ref "J1") (pin "19") (pinfunction "19_19") (pintype "passive"))
    )
    (net (code "102") (name "unconnected-(J1-Pad20)") (class "Default")
      (node (ref "J1") (pin "20") (pinfunction "20_20") (pintype "passive"))
    )
    (net (code "103") (name "unconnected-(J1-Pad21)") (class "Default")
      (node (ref "J1") (pin "21") (pinfunction "21_21") (pintype "passive"))
    )
    (net (code "104") (name "unconnected-(J1-Pad22)") (class "Default")
      (node (ref "J1") (pin "22") (pinfunction "22_22") (pintype "passive"))
    )
    (net (code "105") (name "unconnected-(J2-Pad1)") (class "Default")
      (node (ref "J2") (pin "1") (pinfunction "1_1") (pintype "passive"))
    )
    (net (code "106") (name "unconnected-(J2-Pad12)") (class "Default")
      (node (ref "J2") (pin "12") (pinfunction "12_12") (pintype "passive"))
    )
    (net (code "107") (name "unconnected-(J3-Pad1)") (class "Default")
      (node (ref "J3") (pin "1") (pinfunction "1_1") (pintype "passive"))
    )
    (net (code "108") (name "unconnected-(J3-Pad8)") (class "Default")
      (node (ref "J3") (pin "8") (pinfunction "8_8") (pintype "passive"))
    )
    (net (code "109") (name "unconnected-(J3-Pad9)") (class "Default")
      (node (ref "J3") (pin "9") (pinfunction "9_9") (pintype "passive"))
    )
    (net (code "110") (name "unconnected-(J3-Pad10)") (class "Default")
      (node (ref "J3") (pin "10") (pinfunction "10_10") (pintype "passive"))
    )
    (net (code "111") (name "unconnected-(J3-Pad11)") (class "Default")
      (node (ref "J3") (pin "11") (pinfunction "11_11") (pintype "passive"))
    )
    (net (code "112") (name "unconnected-(J3-Pad12)") (class "Default")
      (node (ref "J3") (pin "12") (pinfunction "12_12") (pintype "passive"))
    )
    (net (code "113") (name "unconnected-(J3-Pad13)") (class "Default")
      (node (ref "J3") (pin "13") (pinfunction "13_13") (pintype "passive"))
    )
    (net (code "114") (name "unconnected-(J3-Pad14)") (class "Default")
      (node (ref "J3") (pin "14") (pinfunction "14_14") (pintype "passive"))
    )
    (net (code "115") (name "unconnected-(J3-Pad15)") (class "Default")
      (node (ref "J3") (pin "15") (pinfunction "15_15") (pintype "passive"))
    )
    (net (code "116") (name "unconnected-(J3-Pad16)") (class "Default")
      (node (ref "J3") (pin "16") (pinfunction "16_16") (pintype "passive"))
    )
    (net (code "117") (name "unconnected-(J4-Pad1)") (class "Default")
      (node (ref "J4") (pin "1") (pinfunction "1_1") (pintype "passive"))
    )
    (net (code "118") (name "unconnected-(J4-Pad10)") (class "Default")
      (node (ref "J4") (pin "10") (pinfunction "10_10") (pintype "passive"))
    )
    (net (code "119") (name "unconnected-(J4-Pad11)") (class "Default")
      (node (ref "J4") (pin "11") (pinfunction "11_11") (pintype "passive"))
    )
    (net (code "120") (name "unconnected-(J4-Pad13)") (class "Default")
      (node (ref "J4") (pin "13") (pinfunction "13_13") (pintype "passive"))
    )
    (net (code "121") (name "unconnected-(J4-Pad14)") (class "Default")
      (node (ref "J4") (pin "14") (pinfunction "14_14") (pintype "passive"))
    )
    (net (code "122") (name "unconnected-(J4-Pad15)") (class "Default")
      (node (ref "J4") (pin "15") (pinfunction "15_15") (pintype "passive"))
    )
    (net (code "123") (name "unconnected-(J4-Pad16)") (class "Default")
      (node (ref "J4") (pin "16") (pinfunction "16_16") (pintype "passive"))
    )
    (net (code "124") (name "unconnected-(J4-Pad17)") (class "Default")
      (node (ref "J4") (pin "17") (pinfunction "17_17") (pintype "passive"))
    )
    (net (code "125") (name "unconnected-(J4-Pad18)") (class "Default")
      (node (ref "J4") (pin "18") (pinfunction "18_18") (pintype "passive"))
    )
    (net (code "126") (name "unconnected-(R5-PadE)") (class "Default")
      (node (ref "R5") (pin "E") (pinfunction "E_E") (pintype "passive"))
    )
    (net (code "127") (name "unconnected-(U$2-Pad4)") (class "Default")
      (node (ref "U$2") (pin "4") (pinfunction "4_4") (pintype "passive"))
    )
    (net (code "128") (name "unconnected-(U$2-Pad11)") (class "Default")
      (node (ref "U$2") (pin "11") (pinfunction "11_11") (pintype "passive"))
    )
    (net (code "129") (name "unconnected-(U$2-Pad12)") (class "Default")
      (node (ref "U$2") (pin "12") (pinfunction "12_12") (pintype "passive"))
    )
    (net (code "130") (name "unconnected-(U$2-Pad15)") (class "Default")
      (node (ref "U$2") (pin "15") (pinfunction "15_15") (pintype "passive"))
    )
  )
)
